# Sheet1.net
KiCad netlist of a schematic drawn in Altium Designer
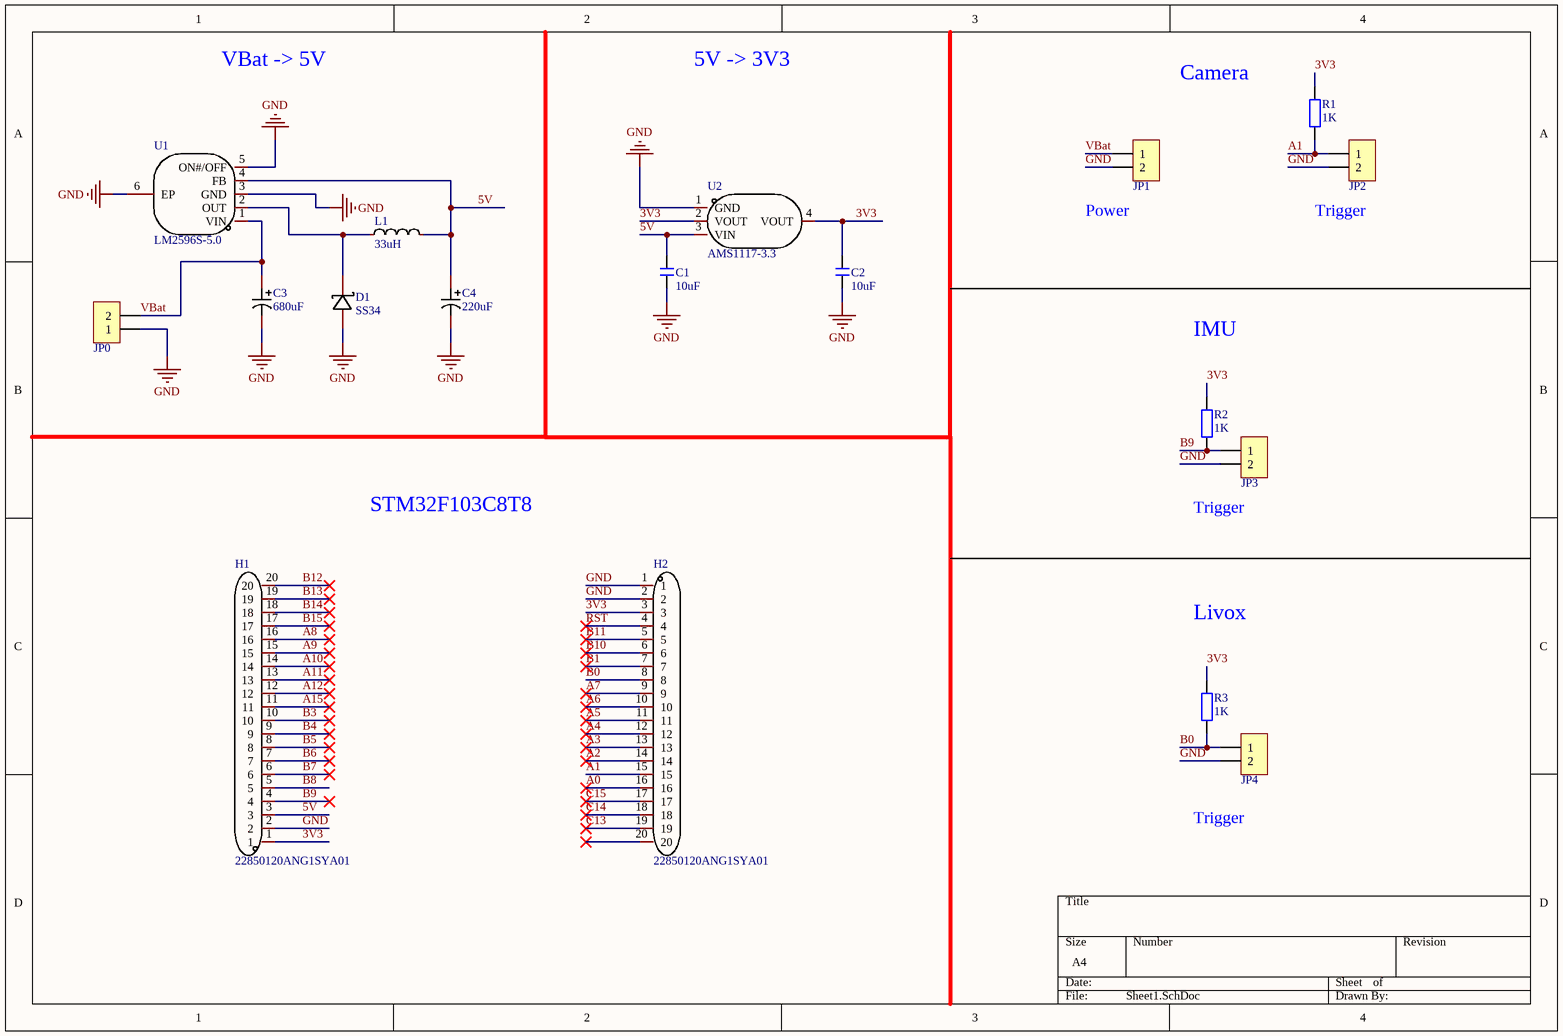
[diagram p0: Sheet1.SchDoc]

(export (version "E")
  (design (tool "Eeschema 10.0.6"))
  (components
    (comp (ref "C1")
      (value "10uF")
      (footprint "C 0805_L")
      (description "无极性贴片电容")
      (fields (field (name "版权归属") "源创客"))
      (libsource (lib "3.1   - 电阻-电容-电感") (part "C"))
    )
    (comp (ref "C2")
      (value "10uF")
      (footprint "C 0805_L")
      (description "无极性贴片电容")
      (fields (field (name "版权归属") "源创客"))
      (libsource (lib "3.1   - 电阻-电容-电感") (part "C"))
    )
    (comp (ref "C3")
      (value "680uF")
      (footprint "CAP-SMD_BD10.0-L10.3-W10.3-LS11.3-FD-1")
      (fields
        (field (name "MANUFACTURER") "DMBJ(振宝佳)")
        (field (name "MANUFACTURER PART") "RVT1E681M1010")
        (field (name "TOLERANCE") "±20%")
        (field (name "NAME") "680uF")
      )
      (libsource (lib "Schlib1") (part "RVT1E681M1010"))
    )
    (comp (ref "C4")
      (value "220uF")
      (footprint "CAP-SMD_BD6.3-L6.6-W6.6-LS7.4-FD")
      (fields
        (field (name "MANUFACTURER") "ROQANG(容强)")
        (field (name "MANUFACTURER PART") "RVT1E221M0607")
        (field (name "TOLERANCE") "±20%")
        (field (name "NAME") "220uF")
      )
      (libsource (lib "Schlib1") (part "RVT1E221M0607"))
    )
    (comp (ref "D1")
      (value "SS34")
      (footprint "DO-214AC_L4.3-W2.7-LS5.3-RD")
      (description "直流反向耐压(Vr):40V;平均整流电流(Io):3A;正向压降(Vf):550mV 3A;")
      (fields (field (name "MANUFACTURER") "MDD") (field (name "NAME") "SS34"))
      (libsource (lib "Schlib1") (part "SS34_C8678"))
    )
    (comp (ref "H1")
      (value "22850120ANG1SYA01")
      (footprint "HDR-TH_20P-P2.54-V-F")
      (description "排数:单排;总孔位数:20;间距:2.54mm;插孔结构:1x20P;行距:-;安装类型:直插;塑高:-;触头材质:黄铜;触头镀层:-;")
      (fields (field (name "MANUFACTURER") "JILN(锦凌)") (field (name "NAME") "22850120ANG1SYA01"))
      (libsource (lib "Schlib1") (part "22850120ANG1SYA01"))
    )
    (comp (ref "H2")
      (value "22850120ANG1SYA01")
      (footprint "HDR-TH_20P-P2.54-V-F")
      (description "排数:单排;总孔位数:20;间距:2.54mm;插孔结构:1x20P;行距:-;安装类型:直插;塑高:-;触头材质:黄铜;触头镀层:-;")
      (fields (field (name "MANUFACTURER") "JILN(锦凌)") (field (name "NAME") "22850120ANG1SYA01"))
      (libsource (lib "Schlib1") (part "22850120ANG1SYA01"))
    )
    (comp (ref "JP0")
      (value "HDR-1X2")
      (footprint "XH2.54-LI-2P")
      (description "2P接插件")
      (fields (field (name "版权归属") "源创客"))
      (libsource (lib "4.5   - 接插件-脚距2.54") (part "Header 2"))
    )
    (comp (ref "JP1")
      (value "HDR-1X2")
      (footprint "XH2.54-LI-2P")
      (description "2P接插件")
      (fields (field (name "版权归属") "源创客"))
      (libsource (lib "") (part "Header 2_1"))
    )
    (comp (ref "JP2")
      (value "HDR-1X2")
      (footprint "XH2.54-LI-2P")
      (description "2P接插件")
      (fields (field (name "版权归属") "源创客"))
      (libsource (lib "") (part "Header 2_1"))
    )
    (comp (ref "JP3")
      (value "HDR-1X2")
      (footprint "XH2.54-LI-2P")
      (description "2P接插件")
      (fields (field (name "版权归属") "源创客"))
      (libsource (lib "") (part "Header 2_1"))
    )
    (comp (ref "JP4")
      (value "HDR-1X2")
      (footprint "XH2.54-LI-2P")
      (description "2P接插件")
      (fields (field (name "版权归属") "源创客"))
      (libsource (lib "") (part "Header 2_1"))
    )
    (comp (ref "L1")
      (value "33uH")
      (footprint "IND-SMD_L12.0-W12.0")
      (description "精度:±20%;直流电阻(DCR):64.8mΩ;电感值:33uH;额定电流:3A;")
      (fields
        (field (name "MANUFACTURER") "Sunltech(韩国顺磁)")
        (field (name "MANUFACTURER PART") "SLH1207S330MTT")
        (field (name "NAME") "33uH")
      )
      (libsource (lib "Schlib1") (part "SLH1207S330MTT"))
    )
    (comp (ref "R1")
      (value "1K")
      (footprint "R 0603_L")
      (description "贴片电阻")
      (fields (field (name "版权归属") "源创客"))
      (libsource (lib "3.1   - 电阻-电容-电感") (part "R"))
    )
    (comp (ref "R2")
      (value "1K")
      (footprint "R 0603_L")
      (description "贴片电阻")
      (fields (field (name "版权归属") "源创客"))
      (libsource (lib "3.1   - 电阻-电容-电感") (part "R"))
    )
    (comp (ref "R3")
      (value "1K")
      (footprint "R 0603_L")
      (description "贴片电阻")
      (fields (field (name "版权归属") "源创客"))
      (libsource (lib "3.1   - 电阻-电容-电感") (part "R"))
    )
    (comp (ref "U1")
      (value "LM2596S-5.0")
      (footprint "TO-263-5_L10.2-W8.9-P1.70-BR")
      (fields (field (name "MANUFACTURER") "UMW(广东友台半导体)") (field (name "NAME") "LM2596S-5.0"))
      (libsource (lib "Schlib1") (part "LM2596S-5.0_C347421"))
    )
    (comp (ref "U2")
      (value "AMS1117-3.3")
      (footprint "SOT-223-3_L6.5-W3.4-P2.30-LS7.0-BR")
      (description "输出类型:固定;输出极性:正;最大输入电压:-;输出电压:3.3V;输出电流:1A;电源纹波抑制比(PSRR):72dB@(120Hz);")
      (fields (field (name "MANUFACTURER") "AMS") (field (name "NAME") "AMS1117-3.3"))
      (libsource (lib "Schlib1") (part "AMS1117-3.3_C6186"))
    )
  )
  (nets
    (net (code "1") (name "/3V3") (class "Default")
      (node (ref "C2") (pin "2") (pinfunction "2_2") (pintype "passive"))
      (node (ref "H1") (pin "1") (pinfunction "1_1") (pintype "passive"))
      (node (ref "H2") (pin "3") (pinfunction "3_3") (pintype "passive"))
      (node (ref "R1") (pin "2") (pinfunction "2_2") (pintype "passive"))
      (node (ref "R2") (pin "2") (pinfunction "2_2") (pintype "passive"))
      (node (ref "R3") (pin "2") (pinfunction "2_2") (pintype "passive"))
      (node (ref "U2") (pin "2") (pinfunction "VOUT_2") (pintype "passive"))
      (node (ref "U2") (pin "4") (pinfunction "VOUT_4") (pintype "passive"))
    )
    (net (code "2") (name "/5V") (class "Default")
      (node (ref "C1") (pin "2") (pinfunction "2_2") (pintype "passive"))
      (node (ref "C4") (pin "1") (pinfunction "1_1") (pintype "passive"))
      (node (ref "H1") (pin "3") (pinfunction "3_3") (pintype "passive"))
      (node (ref "L1") (pin "2") (pinfunction "2_2") (pintype "passive"))
      (node (ref "U1") (pin "4") (pinfunction "FB_4") (pintype "passive"))
      (node (ref "U2") (pin "3") (pinfunction "VIN_3") (pintype "passive"))
    )
    (net (code "3") (name "/A0") (class "Default")
      (node (ref "H2") (pin "16") (pinfunction "16_16") (pintype "passive+no_connect"))
    )
    (net (code "4") (name "/A1") (class "Default")
      (node (ref "H2") (pin "15") (pinfunction "15_15") (pintype "passive"))
      (node (ref "JP2") (pin "1") (pinfunction "1_1") (pintype "passive"))
      (node (ref "R1") (pin "1") (pinfunction "1_1") (pintype "passive"))
    )
    (net (code "5") (name "/A2") (class "Default")
      (node (ref "H2") (pin "14") (pinfunction "14_14") (pintype "passive+no_connect"))
    )
    (net (code "6") (name "/A3") (class "Default")
      (node (ref "H2") (pin "13") (pinfunction "13_13") (pintype "passive+no_connect"))
    )
    (net (code "7") (name "/A4") (class "Default")
      (node (ref "H2") (pin "12") (pinfunction "12_12") (pintype "passive+no_connect"))
    )
    (net (code "8") (name "/A5") (class "Default")
      (node (ref "H2") (pin "11") (pinfunction "11_11") (pintype "passive+no_connect"))
    )
    (net (code "9") (name "/A6") (class "Default")
      (node (ref "H2") (pin "10") (pinfunction "10_10") (pintype "passive+no_connect"))
    )
    (net (code "10") (name "/A7") (class "Default")
      (node (ref "H2") (pin "9") (pinfunction "9_9") (pintype "passive+no_connect"))
    )
    (net (code "11") (name "/A8") (class "Default")
      (node (ref "H1") (pin "16") (pinfunction "16_16") (pintype "passive+no_connect"))
    )
    (net (code "12") (name "/A9") (class "Default")
      (node (ref "H1") (pin "15") (pinfunction "15_15") (pintype "passive+no_connect"))
    )
    (net (code "13") (name "/A10") (class "Default")
      (node (ref "H1") (pin "14") (pinfunction "14_14") (pintype "passive+no_connect"))
    )
    (net (code "14") (name "/A11") (class "Default")
      (node (ref "H1") (pin "13") (pinfunction "13_13") (pintype "passive+no_connect"))
    )
    (net (code "15") (name "/A12") (class "Default")
      (node (ref "H1") (pin "12") (pinfunction "12_12") (pintype "passive+no_connect"))
    )
    (net (code "16") (name "/A15") (class "Default")
      (node (ref "H1") (pin "11") (pinfunction "11_11") (pintype "passive+no_connect"))
    )
    (net (code "17") (name "/B0") (class "Default")
      (node (ref "H2") (pin "8") (pinfunction "8_8") (pintype "passive"))
      (node (ref "JP4") (pin "1") (pinfunction "1_1") (pintype "passive"))
      (node (ref "R3") (pin "1") (pinfunction "1_1") (pintype "passive"))
    )
    (net (code "18") (name "/B1") (class "Default")
      (node (ref "H2") (pin "7") (pinfunction "7_7") (pintype "passive+no_connect"))
    )
    (net (code "19") (name "/B3") (class "Default")
      (node (ref "H1") (pin "10") (pinfunction "10_10") (pintype "passive+no_connect"))
    )
    (net (code "20") (name "/B4") (class "Default")
      (node (ref "H1") (pin "9") (pinfunction "9_9") (pintype "passive+no_connect"))
    )
    (net (code "21") (name "/B5") (class "Default")
      (node (ref "H1") (pin "8") (pinfunction "8_8") (pintype "passive+no_connect"))
    )
    (net (code "22") (name "/B6") (class "Default")
      (node (ref "H1") (pin "7") (pinfunction "7_7") (pintype "passive+no_connect"))
    )
    (net (code "23") (name "/B7") (class "Default")
      (node (ref "H1") (pin "6") (pinfunction "6_6") (pintype "passive+no_connect"))
    )
    (net (code "24") (name "/B8") (class "Default")
      (node (ref "H1") (pin "5") (pinfunction "5_5") (pintype "passive"))
    )
    (net (code "25") (name "/B9") (class "Default")
      (node (ref "H1") (pin "4") (pinfunction "4_4") (pintype "passive"))
      (node (ref "JP3") (pin "1") (pinfunction "1_1") (pintype "passive"))
      (node (ref "R2") (pin "1") (pinfunction "1_1") (pintype "passive"))
    )
    (net (code "26") (name "/B10") (class "Default")
      (node (ref "H2") (pin "6") (pinfunction "6_6") (pintype "passive+no_connect"))
    )
    (net (code "27") (name "/B11") (class "Default")
      (node (ref "H2") (pin "5") (pinfunction "5_5") (pintype "passive+no_connect"))
    )
    (net (code "28") (name "/B12") (class "Default")
      (node (ref "H1") (pin "20") (pinfunction "20_20") (pintype "passive+no_connect"))
    )
    (net (code "29") (name "/B13") (class "Default")
      (node (ref "H1") (pin "19") (pinfunction "19_19") (pintype "passive+no_connect"))
    )
    (net (code "30") (name "/B14") (class "Default")
      (node (ref "H1") (pin "18") (pinfunction "18_18") (pintype "passive+no_connect"))
    )
    (net (code "31") (name "/B15") (class "Default")
      (node (ref "H1") (pin "17") (pinfunction "17_17") (pintype "passive+no_connect"))
    )
    (net (code "32") (name "/C13") (class "Default")
      (node (ref "H2") (pin "19") (pinfunction "19_19") (pintype "passive+no_connect"))
    )
    (net (code "33") (name "/C14") (class "Default")
      (node (ref "H2") (pin "18") (pinfunction "18_18") (pintype "passive+no_connect"))
    )
    (net (code "34") (name "/C15") (class "Default")
      (node (ref "H2") (pin "17") (pinfunction "17_17") (pintype "passive+no_connect"))
    )
    (net (code "35") (name "/RST") (class "Default")
      (node (ref "H2") (pin "4") (pinfunction "4_4") (pintype "passive+no_connect"))
    )
    (net (code "36") (name "/VBat") (class "Default")
      (node (ref "C3") (pin "1") (pinfunction "1_1") (pintype "passive"))
      (node (ref "JP0") (pin "2") (pinfunction "2_2") (pintype "passive"))
      (node (ref "JP1") (pin "1") (pinfunction "1_1") (pintype "passive"))
      (node (ref "U1") (pin "1") (pinfunction "VIN_1") (pintype "passive"))
    )
    (net (code "37") (name "GND") (class "Default")
      (node (ref "C1") (pin "1") (pinfunction "1_1") (pintype "passive"))
      (node (ref "C2") (pin "1") (pinfunction "1_1") (pintype "passive"))
      (node (ref "C3") (pin "2") (pinfunction "2_2") (pintype "passive"))
      (node (ref "C4") (pin "2") (pinfunction "2_2") (pintype "passive"))
      (node (ref "D1") (pin "2") (pinfunction "A_2") (pintype "passive"))
      (node (ref "H1") (pin "2") (pinfunction "2_2") (pintype "passive"))
      (node (ref "H2") (pin "1") (pinfunction "1_1") (pintype "passive"))
      (node (ref "H2") (pin "2") (pinfunction "2_2") (pintype "passive"))
      (node (ref "JP0") (pin "1") (pinfunction "1_1") (pintype "passive"))
      (node (ref "JP1") (pin "2") (pinfunction "2_2") (pintype "passive"))
      (node (ref "JP2") (pin "2") (pinfunction "2_2") (pintype "passive"))
      (node (ref "JP3") (pin "2") (pinfunction "2_2") (pintype "passive"))
      (node (ref "JP4") (pin "2") (pinfunction "2_2") (pintype "passive"))
      (node (ref "U1") (pin "3") (pinfunction "GND_3") (pintype "passive"))
      (node (ref "U1") (pin "5") (pinfunction "ON#/OFF_5") (pintype "passive"))
      (node (ref "U1") (pin "6") (pinfunction "EP_6") (pintype "passive"))
      (node (ref "U2") (pin "1") (pinfunction "GND_1") (pintype "passive"))
    )
    (net (code "38") (name "Net-(D1-K)") (class "Default")
      (node (ref "D1") (pin "1") (pinfunction "K_1") (pintype "passive"))
      (node (ref "L1") (pin "1") (pinfunction "1_1") (pintype "passive"))
      (node (ref "U1") (pin "2") (pinfunction "OUT_2") (pintype "passive"))
    )
    (net (code "39") (name "unconnected-(H2-Pad20)") (class "Default")
      (node (ref "H2") (pin "20") (pinfunction "20_20") (pintype "passive+no_connect"))
    )
  )
)
